# 01_MICRO.net
KiCad netlist of a schematic drawn in Altium Designer
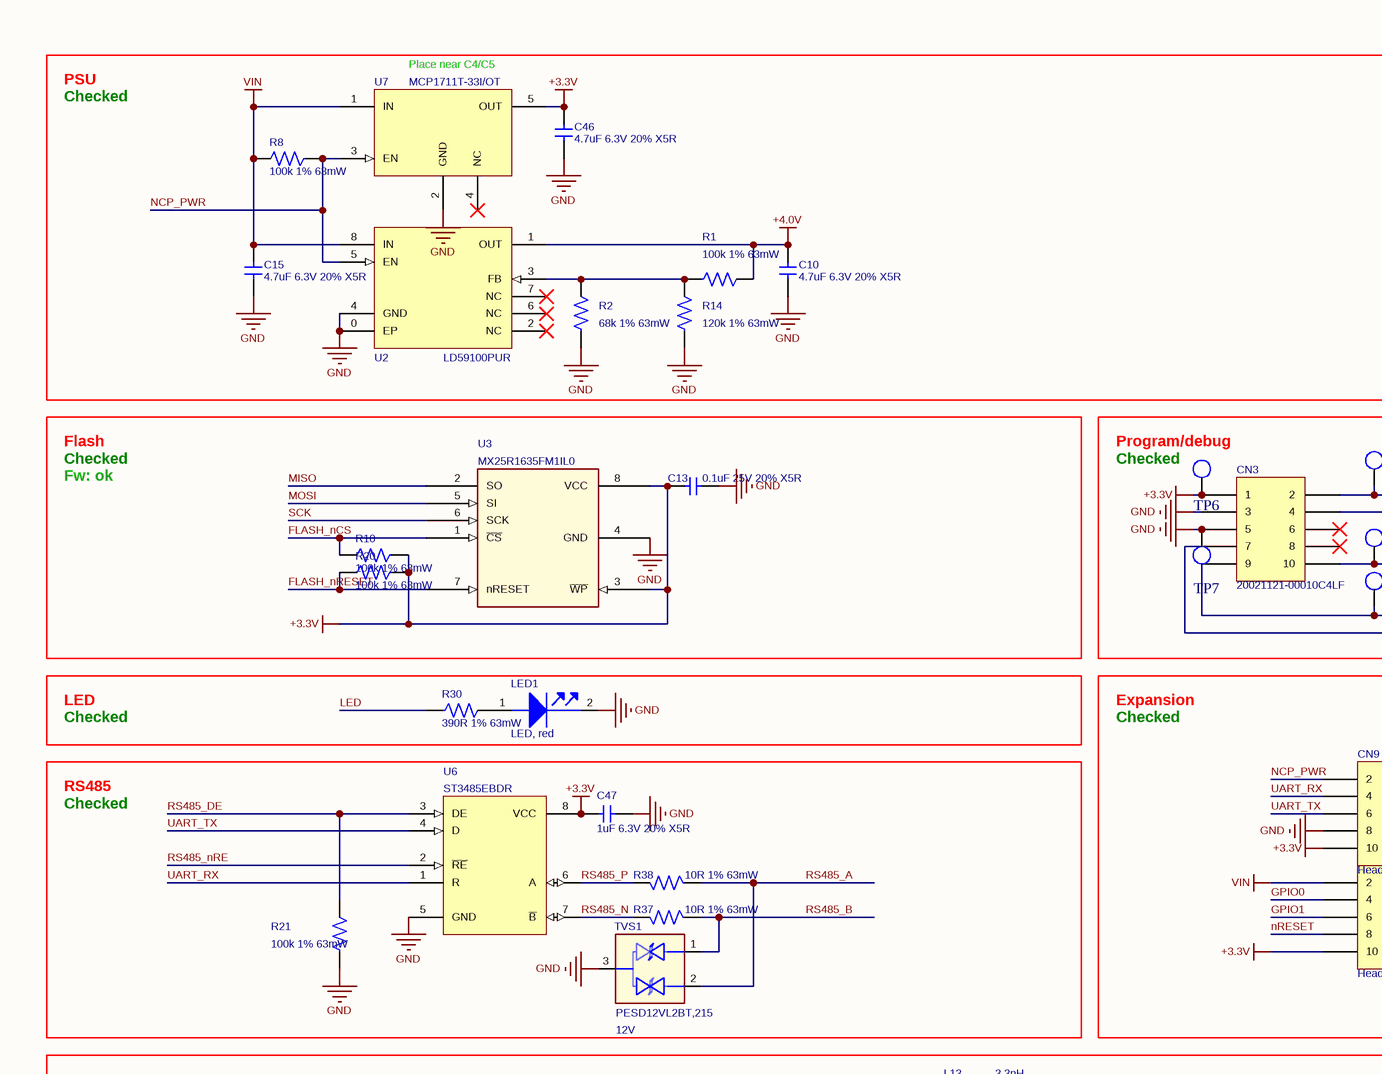
[diagram p0: 01_MICRO.SchDoc, top left]
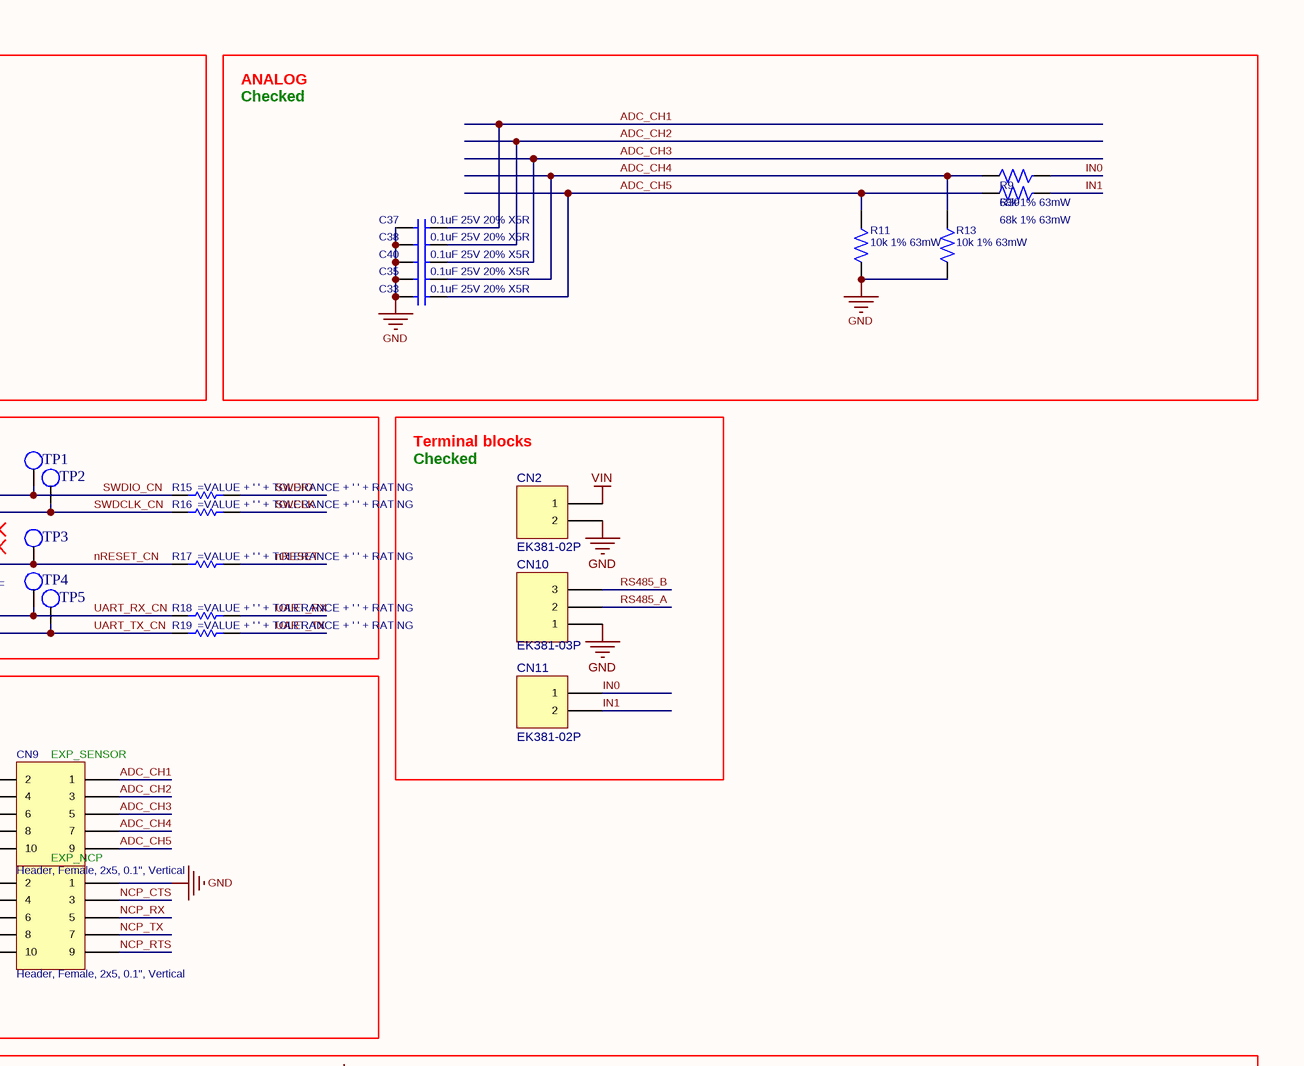
[diagram p1: 01_MICRO.SchDoc, top right]
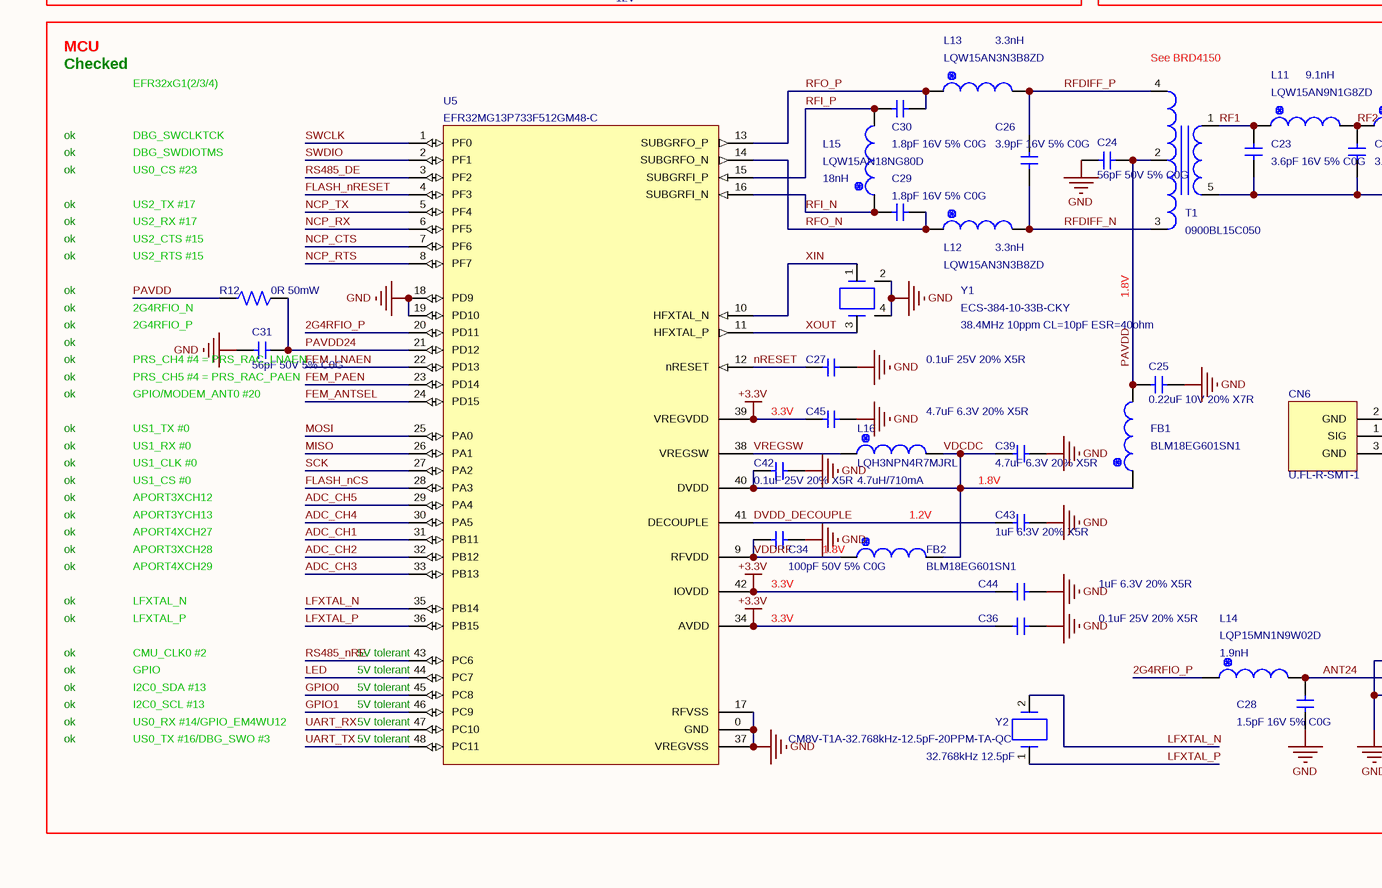
[diagram p2: 01_MICRO.SchDoc, bottom left]
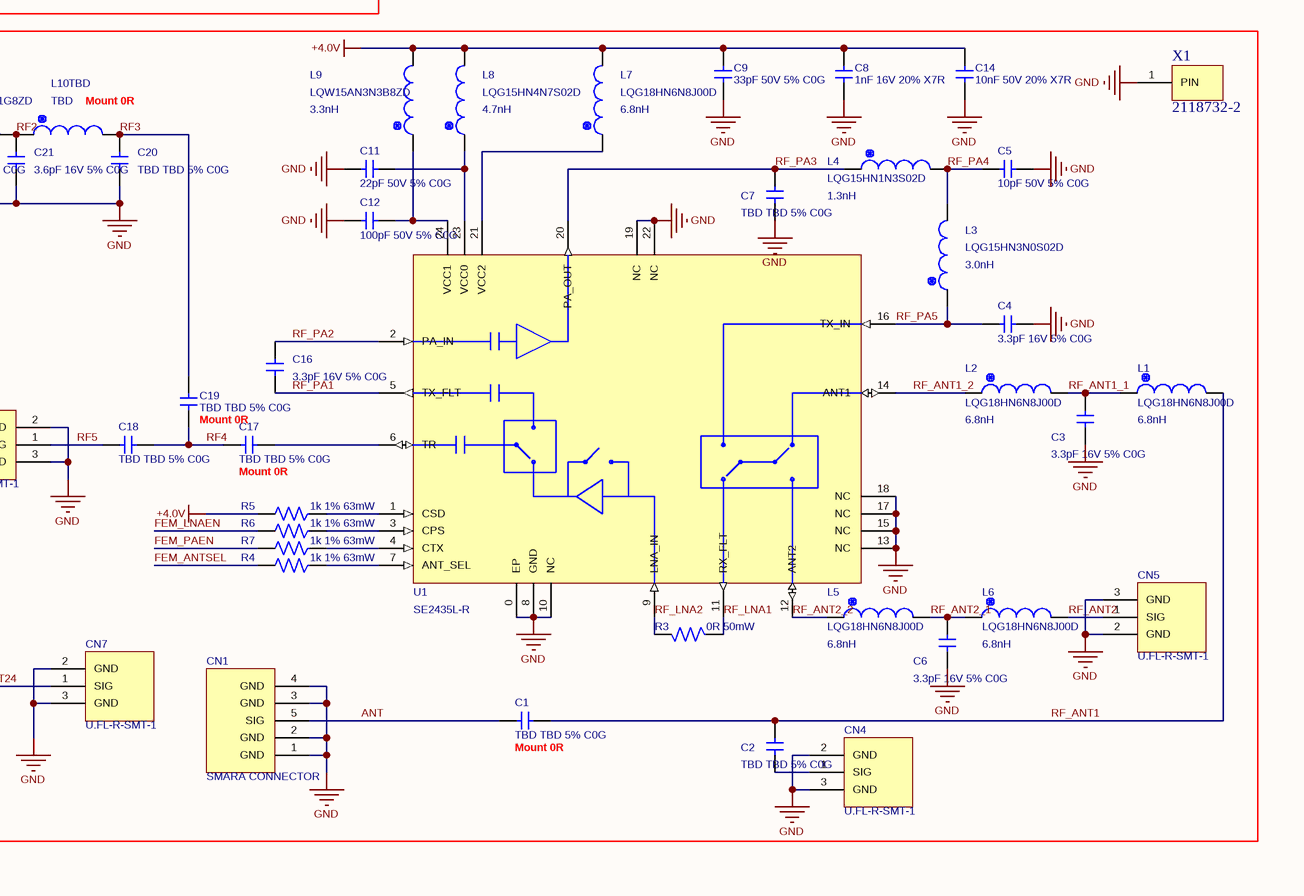
[diagram p3: 01_MICRO.SchDoc, bottom right]

(export (version "E")
  (design (tool "Eeschema 10.0.6"))
  (components
    (comp (ref "C1")
      (value "TBD TBD 5% C0G")
      (footprint "CAPC1005X55L")
      (description "Capacitor, ceramic")
      (fields
        (field (name "MFG") "<GENERIC>")
        (field (name "ASSEMBLYCOMMENTS") "Mount 0R")
        (field (name "TOLERANCE") "5%")
        (field (name "FOOTPRINT CHECKED") "Assign OK, Footprint OK")
      )
      (libsource (lib "*") (part "C_Dup1"))
    )
    (comp (ref "C2")
      (value "TBD TBD 5% C0G")
      (footprint "CAPC1005X55L")
      (description "Capacitor, ceramic")
      (fields
        (field (name "MFG") "<GENERIC>")
        (field (name "TOLERANCE") "5%")
        (field (name "FOOTPRINT CHECKED") "Assign OK, Footprint OK")
      )
      (libsource (lib "*") (part "C_Dup1"))
    )
    (comp (ref "C3")
      (value "3.3pF 16V 5% C0G")
      (footprint "CAPC1005X55L")
      (description "Capacitor, ceramic")
      (fields
        (field (name "MFG") "YAGEO")
        (field (name "TOLERANCE") "5%")
        (field (name "FOOTPRINT CHECKED") "Assign OK, Footprint OK")
      )
      (libsource (lib "*") (part "C_Dup1"))
    )
    (comp (ref "C4")
      (value "3.3pF 16V 5% C0G")
      (footprint "CAPC1005X55L")
      (description "Capacitor, ceramic")
      (fields
        (field (name "MFG") "YAGEO")
        (field (name "TOLERANCE") "5%")
        (field (name "FOOTPRINT CHECKED") "Assign OK, Footprint OK")
      )
      (libsource (lib "*") (part "C_Dup1"))
    )
    (comp (ref "C5")
      (value "10pF 50V 5% C0G")
      (footprint "CAPC1005X55L")
      (description "Capacitor, ceramic")
      (fields
        (field (name "MFG") "SAMSUNG")
        (field (name "TOLERANCE") "5%")
        (field (name "FOOTPRINT CHECKED") "Assign OK, Footprint OK")
      )
      (libsource (lib "*") (part "C_Dup1"))
    )
    (comp (ref "C6")
      (value "3.3pF 16V 5% C0G")
      (footprint "CAPC1005X55L")
      (description "Capacitor, ceramic")
      (fields
        (field (name "MFG") "YAGEO")
        (field (name "TOLERANCE") "5%")
        (field (name "FOOTPRINT CHECKED") "Assign OK, Footprint OK")
      )
      (libsource (lib "*") (part "C_Dup1"))
    )
    (comp (ref "C7")
      (value "TBD TBD 5% C0G")
      (footprint "CAPC1005X55L")
      (description "Capacitor, ceramic")
      (fields
        (field (name "MFG") "<GENERIC>")
        (field (name "TOLERANCE") "5%")
        (field (name "FOOTPRINT CHECKED") "Assign OK, Footprint OK")
      )
      (libsource (lib "*") (part "C_Dup1"))
    )
    (comp (ref "C8")
      (value "1nF 16V 20% X7R")
      (footprint "CAPC1005X55L")
      (description "Capacitor, ceramic")
      (fields
        (field (name "MFG") "SAMSUNG")
        (field (name "TOLERANCE") "20%")
        (field (name "FOOTPRINT CHECKED") "Assign OK, Footprint OK")
      )
      (libsource (lib "*") (part "C_Dup1"))
    )
    (comp (ref "C9")
      (value "33pF 50V 5% C0G")
      (footprint "CAPC1005X55L")
      (description "Capacitor, ceramic")
      (fields
        (field (name "MFG") "SAMSUNG")
        (field (name "TOLERANCE") "5%")
        (field (name "FOOTPRINT CHECKED") "Assign OK, Footprint OK")
      )
      (libsource (lib "*") (part "C_Dup1"))
    )
    (comp (ref "C10")
      (value "4.7uF 6.3V 20% X5R")
      (footprint "CAPC1608X90N")
      (description "Capacitor, ceramic")
      (fields
        (field (name "MFG") "SAMSUNG")
        (field (name "TOLERANCE") "20%")
        (field (name "FOOTPRINT CHECKED") "Assign OK, Footprint OK")
      )
      (libsource (lib "*") (part "C_Dup1"))
    )
    (comp (ref "C11")
      (value "22pF 50V 5% C0G")
      (footprint "CAPC1005X55L")
      (description "Capacitor, ceramic")
      (fields
        (field (name "MFG") "SAMSUNG")
        (field (name "TOLERANCE") "5%")
        (field (name "FOOTPRINT CHECKED") "Assign OK, Footprint OK")
      )
      (libsource (lib "*") (part "C_Dup1"))
    )
    (comp (ref "C12")
      (value "100pF 50V 5% C0G")
      (footprint "CAPC1005X55L")
      (description "Capacitor, ceramic")
      (fields
        (field (name "MFG") "SAMSUNG")
        (field (name "TOLERANCE") "5%")
        (field (name "FOOTPRINT CHECKED") "Assign OK, Footprint OK")
      )
      (libsource (lib "*") (part "C_Dup1"))
    )
    (comp (ref "C13")
      (value "0.1uF 25V 20% X5R")
      (footprint "CAPC1005N")
      (description "Capacitor, ceramic")
      (fields
        (field (name "MFG") "SAMSUNG")
        (field (name "TOLERANCE") "20%")
        (field (name "FOOTPRINT CHECKED") "Assign OK, Footprint OK")
      )
      (libsource (lib "*") (part "C_Dup1"))
    )
    (comp (ref "C14")
      (value "10nF 50V 20% X7R")
      (footprint "CAPC1005X55L")
      (description "Capacitor, ceramic")
      (fields
        (field (name "MFG") "SAMSUNG")
        (field (name "TOLERANCE") "20%")
        (field (name "FOOTPRINT CHECKED") "Assign OK, Footprint OK")
      )
      (libsource (lib "*") (part "C_Dup1"))
    )
    (comp (ref "C15")
      (value "4.7uF 6.3V 20% X5R")
      (footprint "CAPC1608X90N")
      (description "Capacitor, ceramic")
      (fields
        (field (name "MFG") "SAMSUNG")
        (field (name "TOLERANCE") "20%")
        (field (name "FOOTPRINT CHECKED") "Assign OK, Footprint OK")
      )
      (libsource (lib "*") (part "C_Dup1"))
    )
    (comp (ref "C16")
      (value "3.3pF 16V 5% C0G")
      (footprint "CAPC1005X55L")
      (description "Capacitor, ceramic")
      (fields
        (field (name "MFG") "YAGEO")
        (field (name "TOLERANCE") "5%")
        (field (name "FOOTPRINT CHECKED") "Assign OK, Footprint OK")
      )
      (libsource (lib "*") (part "C_Dup1"))
    )
    (comp (ref "C17")
      (value "TBD TBD 5% C0G")
      (footprint "CAPC1005X55L")
      (description "Capacitor, ceramic")
      (fields
        (field (name "MFG") "<GENERIC>")
        (field (name "ASSEMBLYCOMMENTS") "Mount 0R")
        (field (name "TOLERANCE") "5%")
        (field (name "FOOTPRINT CHECKED") "Assign OK, Footprint OK")
      )
      (libsource (lib "*") (part "C_Dup1"))
    )
    (comp (ref "C18")
      (value "TBD TBD 5% C0G")
      (footprint "CAPC1005X55L")
      (description "Capacitor, ceramic")
      (fields
        (field (name "MFG") "<GENERIC>")
        (field (name "TOLERANCE") "5%")
        (field (name "FOOTPRINT CHECKED") "Assign OK, Footprint OK")
      )
      (libsource (lib "*") (part "C_Dup1"))
    )
    (comp (ref "C19")
      (value "TBD TBD 5% C0G")
      (footprint "CAPC1005X55L")
      (description "Capacitor, ceramic")
      (fields
        (field (name "MFG") "<GENERIC>")
        (field (name "ASSEMBLYCOMMENTS") "Mount 0R")
        (field (name "TOLERANCE") "5%")
        (field (name "FOOTPRINT CHECKED") "Assign OK, Footprint OK")
      )
      (libsource (lib "*") (part "C_Dup1"))
    )
    (comp (ref "C20")
      (value "TBD TBD 5% C0G")
      (footprint "CAPC1005X55L")
      (description "Capacitor, ceramic")
      (fields
        (field (name "MFG") "<GENERIC>")
        (field (name "TOLERANCE") "5%")
        (field (name "FOOTPRINT CHECKED") "Assign OK, Footprint OK")
      )
      (libsource (lib "*") (part "C_Dup1"))
    )
    (comp (ref "C21")
      (value "3.6pF 16V 5% C0G")
      (footprint "CAPC1005X55L")
      (description "Capacitor, ceramic")
      (fields
        (field (name "MFG") "YAGEO")
        (field (name "TOLERANCE") "5%")
        (field (name "FOOTPRINT CHECKED") "Assign OK, Footprint OK")
      )
      (libsource (lib "*") (part "C_Dup1"))
    )
    (comp (ref "C23")
      (value "3.6pF 16V 5% C0G")
      (footprint "CAPC1005X55L")
      (description "Capacitor, ceramic")
      (fields
        (field (name "MFG") "YAGEO")
        (field (name "TOLERANCE") "5%")
        (field (name "FOOTPRINT CHECKED") "Assign OK, Footprint OK")
      )
      (libsource (lib "*") (part "C_Dup1"))
    )
    (comp (ref "C24")
      (value "56pF 50V 5% C0G")
      (footprint "CAPC1005X55L")
      (description "Capacitor, ceramic")
      (fields
        (field (name "MFG") "SAMSUNG")
        (field (name "TOLERANCE") "5%")
        (field (name "FOOTPRINT CHECKED") "Assign OK, Footprint OK")
      )
      (libsource (lib "*") (part "C_Dup1"))
    )
    (comp (ref "C25")
      (value "0.22uF 10V 20% X7R")
      (footprint "CAPC1005N")
      (description "Capacitor, ceramic")
      (fields
        (field (name "MFG") "SAMSUNG")
        (field (name "TOLERANCE") "20%")
        (field (name "FOOTPRINT CHECKED") "Assign OK, Footprint OK")
      )
      (libsource (lib "*") (part "C_Dup1"))
    )
    (comp (ref "C26")
      (value "3.9pF 16V 5% C0G")
      (footprint "CAPC1005X55L")
      (description "Capacitor, ceramic")
      (fields
        (field (name "MFG") "YAGEO")
        (field (name "TOLERANCE") "5%")
        (field (name "FOOTPRINT CHECKED") "Assign OK, Footprint OK")
      )
      (libsource (lib "*") (part "C_Dup1"))
    )
    (comp (ref "C27")
      (value "0.1uF 25V 20% X5R")
      (footprint "CAPC1005N")
      (description "Capacitor, ceramic")
      (fields
        (field (name "MFG") "SAMSUNG")
        (field (name "TOLERANCE") "20%")
        (field (name "FOOTPRINT CHECKED") "Assign OK, Footprint OK")
      )
      (libsource (lib "*") (part "C_Dup1"))
    )
    (comp (ref "C28")
      (value "1.5pF 16V 5% C0G")
      (footprint "CAPC1005X55L")
      (description "Capacitor, ceramic")
      (fields
        (field (name "MFG") "YAGEO")
        (field (name "TOLERANCE") "5%")
        (field (name "FOOTPRINT CHECKED") "Assign OK, Footprint OK")
      )
      (libsource (lib "*") (part "C_Dup1"))
    )
    (comp (ref "C29")
      (value "1.8pF 16V 5% C0G")
      (footprint "CAPC1005X55L")
      (description "Capacitor, ceramic")
      (fields
        (field (name "MFG") "YAGEO")
        (field (name "TOLERANCE") "5%")
        (field (name "FOOTPRINT CHECKED") "Assign OK, Footprint OK")
      )
      (libsource (lib "*") (part "C_Dup1"))
    )
    (comp (ref "C30")
      (value "1.8pF 16V 5% C0G")
      (footprint "CAPC1005X55L")
      (description "Capacitor, ceramic")
      (fields
        (field (name "MFG") "YAGEO")
        (field (name "TOLERANCE") "5%")
        (field (name "FOOTPRINT CHECKED") "Assign OK, Footprint OK")
      )
      (libsource (lib "*") (part "C_Dup1"))
    )
    (comp (ref "C31")
      (value "56pF 50V 5% C0G")
      (footprint "CAPC1005X55L")
      (description "Capacitor, ceramic")
      (fields
        (field (name "MFG") "SAMSUNG")
        (field (name "TOLERANCE") "5%")
        (field (name "FOOTPRINT CHECKED") "Assign OK, Footprint OK")
      )
      (libsource (lib "*") (part "C_Dup1"))
    )
    (comp (ref "C33")
      (value "0.1uF 25V 20% X5R")
      (footprint "CAPC1005N")
      (description "Capacitor, ceramic")
      (fields
        (field (name "MFG") "SAMSUNG")
        (field (name "TOLERANCE") "20%")
        (field (name "FOOTPRINT CHECKED") "Assign OK, Footprint OK")
      )
      (libsource (lib "*") (part "C_Dup1"))
    )
    (comp (ref "C34")
      (value "100pF 50V 5% C0G")
      (footprint "CAPC1005X55L")
      (description "Capacitor, ceramic")
      (fields
        (field (name "MFG") "SAMSUNG")
        (field (name "TOLERANCE") "5%")
        (field (name "FOOTPRINT CHECKED") "Assign OK, Footprint OK")
      )
      (libsource (lib "*") (part "C_Dup1"))
    )
    (comp (ref "C35")
      (value "0.1uF 25V 20% X5R")
      (footprint "CAPC1005N")
      (description "Capacitor, ceramic")
      (fields
        (field (name "MFG") "SAMSUNG")
        (field (name "TOLERANCE") "20%")
        (field (name "FOOTPRINT CHECKED") "Assign OK, Footprint OK")
      )
      (libsource (lib "*") (part "C_Dup1"))
    )
    (comp (ref "C36")
      (value "0.1uF 25V 20% X5R")
      (footprint "CAPC1005N")
      (description "Capacitor, ceramic")
      (fields
        (field (name "MFG") "SAMSUNG")
        (field (name "TOLERANCE") "20%")
        (field (name "FOOTPRINT CHECKED") "Assign OK, Footprint OK")
      )
      (libsource (lib "*") (part "C_Dup1"))
    )
    (comp (ref "C37")
      (value "0.1uF 25V 20% X5R")
      (footprint "CAPC1005N")
      (description "Capacitor, ceramic")
      (fields
        (field (name "MFG") "SAMSUNG")
        (field (name "TOLERANCE") "20%")
        (field (name "FOOTPRINT CHECKED") "Assign OK, Footprint OK")
      )
      (libsource (lib "*") (part "C_Dup1"))
    )
    (comp (ref "C38")
      (value "0.1uF 25V 20% X5R")
      (footprint "CAPC1005N")
      (description "Capacitor, ceramic")
      (fields
        (field (name "MFG") "SAMSUNG")
        (field (name "TOLERANCE") "20%")
        (field (name "FOOTPRINT CHECKED") "Assign OK, Footprint OK")
      )
      (libsource (lib "*") (part "C_Dup1"))
    )
    (comp (ref "C39")
      (value "4.7uF 6.3V 20% X5R")
      (footprint "CAPC1608X90N")
      (description "Capacitor, ceramic")
      (fields
        (field (name "MFG") "SAMSUNG")
        (field (name "TOLERANCE") "20%")
        (field (name "FOOTPRINT CHECKED") "Assign OK, Footprint OK")
      )
      (libsource (lib "*") (part "C_Dup1"))
    )
    (comp (ref "C40")
      (value "0.1uF 25V 20% X5R")
      (footprint "CAPC1005N")
      (description "Capacitor, ceramic")
      (fields
        (field (name "MFG") "SAMSUNG")
        (field (name "TOLERANCE") "20%")
        (field (name "FOOTPRINT CHECKED") "Assign OK, Footprint OK")
      )
      (libsource (lib "*") (part "C_Dup1"))
    )
    (comp (ref "C42")
      (value "0.1uF 25V 20% X5R")
      (footprint "CAPC1005N")
      (description "Capacitor, ceramic")
      (fields
        (field (name "MFG") "SAMSUNG")
        (field (name "TOLERANCE") "20%")
        (field (name "FOOTPRINT CHECKED") "Assign OK, Footprint OK")
      )
      (libsource (lib "*") (part "C_Dup1"))
    )
    (comp (ref "C43")
      (value "1uF 6.3V 20% X5R")
      (footprint "CAPC1005N")
      (description "Capacitor, ceramic")
      (fields
        (field (name "MFG") "SAMSUNG")
        (field (name "TOLERANCE") "20%")
        (field (name "FOOTPRINT CHECKED") "Assign OK, Footprint OK")
      )
      (libsource (lib "*") (part "C_Dup1"))
    )
    (comp (ref "C44")
      (value "1uF 6.3V 20% X5R")
      (footprint "CAPC1005N")
      (description "Capacitor, ceramic")
      (fields
        (field (name "MFG") "SAMSUNG")
        (field (name "TOLERANCE") "20%")
        (field (name "FOOTPRINT CHECKED") "Assign OK, Footprint OK")
      )
      (libsource (lib "*") (part "C_Dup1"))
    )
    (comp (ref "C45")
      (value "4.7uF 6.3V 20% X5R")
      (footprint "CAPC1608X90N")
      (description "Capacitor, ceramic")
      (fields
        (field (name "MFG") "SAMSUNG")
        (field (name "TOLERANCE") "20%")
        (field (name "FOOTPRINT CHECKED") "Assign OK, Footprint OK")
      )
      (libsource (lib "*") (part "C_Dup1"))
    )
    (comp (ref "C46")
      (value "4.7uF 6.3V 20% X5R")
      (footprint "CAPC1608X90N")
      (description "Capacitor, ceramic")
      (fields
        (field (name "MFG") "SAMSUNG")
        (field (name "TOLERANCE") "20%")
        (field (name "FOOTPRINT CHECKED") "Assign OK, Footprint OK")
      )
      (libsource (lib "*") (part "C_Dup1"))
    )
    (comp (ref "C47")
      (value "1uF 6.3V 20% X5R")
      (footprint "CAPC1005N")
      (description "Capacitor, ceramic")
      (fields
        (field (name "MFG") "SAMSUNG")
        (field (name "TOLERANCE") "20%")
        (field (name "FOOTPRINT CHECKED") "Assign OK, Footprint OK")
      )
      (libsource (lib "*") (part "C_Dup1"))
    )
    (comp (ref "CN1")
      (value "SMARA CONNECTOR")
      (footprint "0733910320")
      (description "SMA, Right angle")
      (fields (field (name "MFG") "LPRS") (field (name "FOOTPRINT CHECKED") "Assign OK, Footprint OK"))
      (libsource (lib "xct") (part "RPSMA"))
    )
    (comp (ref "CN2")
      (value "EK381-02P")
      (footprint "EK381-02P")
      (description "Header, 2-Pin")
      (fields (field (name "MFG") "DINKLE") (field (name "FOOTPRINT CHECKED") "Assign OK, Footprint OK"))
      (libsource (lib "Miscellaneous Connectors") (part "Header 2"))
    )
    (comp (ref "CN3")
      (value "20021121-00010C4LF")
      (footprint "SensorWireless:HDR2X5")
      (description "Connector Header Surface Mount 10 position 0.050\" (1.27mm)")
      (fields (field (name "MFG") "AMPHENOL") (field (name "FOOTPRINT CHECKED") "Assign Ok, Footprint Ok"))
      (libsource (lib "") (part "Header 5X2_1"))
    )
    (comp (ref "CN4")
      (value "U.FL-R-SMT-1")
      (footprint "U.FL-R-SMT-1")
      (description "Ultra Small Surface Mount Coaxial Connectors - 1.9mm or 2.4mm Mated Height")
      (fields (field (name "MFG") "HIROSE") (field (name "FOOTPRINT CHECKED") "Assign OK, Footprint OK"))
      (libsource (lib "") (part "U.FL-R-SMT-1_1"))
    )
    (comp (ref "CN5")
      (value "U.FL-R-SMT-1")
      (footprint "U.FL-R-SMT-1")
      (description "Ultra Small Surface Mount Coaxial Connectors - 1.9mm or 2.4mm Mated Height")
      (fields (field (name "MFG") "HIROSE") (field (name "FOOTPRINT CHECKED") "Assign OK, Footprint OK"))
      (libsource (lib "traz") (part "U.FL-R-SMT-1"))
    )
    (comp (ref "CN6")
      (value "U.FL-R-SMT-1")
      (footprint "U.FL-R-SMT-1")
      (description "Ultra Small Surface Mount Coaxial Connectors - 1.9mm or 2.4mm Mated Height")
      (fields (field (name "MFG") "HIROSE") (field (name "FOOTPRINT CHECKED") "Assign OK, Footprint OK"))
      (libsource (lib "") (part "U.FL-R-SMT-1_2"))
    )
    (comp (ref "CN7")
      (value "U.FL-R-SMT-1")
      (footprint "U.FL-R-SMT-1")
      (description "Ultra Small Surface Mount Coaxial Connectors - 1.9mm or 2.4mm Mated Height")
      (fields (field (name "MFG") "HIROSE") (field (name "FOOTPRINT CHECKED") "Assign OK, Footprint OK"))
      (libsource (lib "") (part "U.FL-R-SMT-1_1"))
    )
    (comp (ref "CN8")
      (value "Header, Female, 2x5, 0.1\", Vertical")
      (fields (field (name "MFG") "<GENERIC>") (field (name "FOOTPRINT CHECKED") "Assign Ok, Footprint Ok"))
      (libsource (lib "Miscellaneous Connectors") (part "Header 5X2"))
    )
    (comp (ref "CN9")
      (value "Header, Female, 2x5, 0.1\", Vertical")
      (fields (field (name "MFG") "<GENERIC>") (field (name "FOOTPRINT CHECKED") "Assign Ok, Footprint Ok"))
      (libsource (lib "Miscellaneous Connectors") (part "Header 5X2"))
    )
    (comp (ref "CN10")
      (value "EK381-03P")
      (footprint "EK381-03P")
      (description "Header, 3-Pin")
      (fields (field (name "MFG") "DINKLE") (field (name "FOOTPRINT CHECKED") "Assign OK, Footprint OK"))
      (libsource (lib "Miscellaneous Connectors") (part "Header 3"))
    )
    (comp (ref "CN11")
      (value "EK381-02P")
      (footprint "EK381-02P")
      (description "Header, 2-Pin")
      (fields (field (name "MFG") "DINKLE") (field (name "FOOTPRINT CHECKED") "Assign OK, Footprint OK"))
      (libsource (lib "Miscellaneous Connectors") (part "Header 2"))
    )
    (comp (ref "FB1")
      (value "BLM18EG601SN1")
      (footprint "INDC1608X95N")
      (description "Ferrite bead")
      (fields (field (name "MFG") "MURATA") (field (name "FOOTPRINT CHECKED") "Assign OK, Footprint OK"))
      (libsource (lib "*") (part "L"))
    )
    (comp (ref "FB2")
      (value "BLM18EG601SN1")
      (footprint "INDC1608X95N")
      (description "Ferrite bead")
      (fields (field (name "MFG") "MURATA") (field (name "FOOTPRINT CHECKED") "Assign OK, Footprint OK"))
      (libsource (lib "*") (part "L"))
    )
    (comp (ref "L1")
      (value "LQG18HN6N8J00D")
      (footprint "INDC1608X95N")
      (description "Inductor")
      (fields
        (field (name "MFG") "MURATA")
        (field (name "ALTIUM_VALUE") "6.8nH")
        (field (name "TOLERANCE") "TBD%")
        (field (name "FOOTPRINT CHECKED") "Assign OK, Footprint OK")
      )
      (libsource (lib "*") (part "L"))
    )
    (comp (ref "L2")
      (value "LQG18HN6N8J00D")
      (footprint "INDC1608X95N")
      (description "Inductor")
      (fields
        (field (name "MFG") "MURATA")
        (field (name "ALTIUM_VALUE") "6.8nH")
        (field (name "TOLERANCE") "TBD%")
        (field (name "FOOTPRINT CHECKED") "Assign OK, Footprint OK")
      )
      (libsource (lib "*") (part "L"))
    )
    (comp (ref "L3")
      (value "LQG15HN3N0S02D")
      (footprint "INDC1005X55L")
      (description "Inductor")
      (fields
        (field (name "MFG") "MURATA")
        (field (name "ALTIUM_VALUE") "3.0nH")
        (field (name "TOLERANCE") "TBD%")
        (field (name "FOOTPRINT CHECKED") "Assign OK, Footprint OK")
      )
      (libsource (lib "*") (part "L"))
    )
    (comp (ref "L4")
      (value "LQG15HN1N3S02D")
      (footprint "INDC1005X55L")
      (description "Inductor")
      (fields
        (field (name "MFG") "MURATA")
        (field (name "ALTIUM_VALUE") "1.3nH")
        (field (name "TOLERANCE") "TBD%")
        (field (name "FOOTPRINT CHECKED") "Assign OK, Footprint OK")
      )
      (libsource (lib "*") (part "L"))
    )
    (comp (ref "L5")
      (value "LQG18HN6N8J00D")
      (footprint "INDC1608X95N")
      (description "Inductor")
      (fields
        (field (name "MFG") "MURATA")
        (field (name "ALTIUM_VALUE") "6.8nH")
        (field (name "TOLERANCE") "TBD%")
        (field (name "FOOTPRINT CHECKED") "Assign OK, Footprint OK")
      )
      (libsource (lib "*") (part "L"))
    )
    (comp (ref "L6")
      (value "LQG18HN6N8J00D")
      (footprint "INDC1608X95N")
      (description "Inductor")
      (fields
        (field (name "MFG") "MURATA")
        (field (name "ALTIUM_VALUE") "6.8nH")
        (field (name "TOLERANCE") "TBD%")
        (field (name "FOOTPRINT CHECKED") "Assign OK, Footprint OK")
      )
      (libsource (lib "*") (part "L"))
    )
    (comp (ref "L7")
      (value "LQG18HN6N8J00D")
      (footprint "INDC1608X95N")
      (description "Inductor")
      (fields
        (field (name "MFG") "MURATA")
        (field (name "ALTIUM_VALUE") "6.8nH")
        (field (name "TOLERANCE") "TBD%")
        (field (name "FOOTPRINT CHECKED") "Assign OK, Footprint OK")
      )
      (libsource (lib "*") (part "L"))
    )
    (comp (ref "L8")
      (value "LQG15HN4N7S02D")
      (footprint "INDC1005X55L")
      (description "Inductor")
      (fields
        (field (name "MFG") "MURATA")
        (field (name "ALTIUM_VALUE") "4.7nH")
        (field (name "TOLERANCE") "TBD%")
        (field (name "FOOTPRINT CHECKED") "Assign OK, Footprint OK")
      )
      (libsource (lib "*") (part "L"))
    )
    (comp (ref "L9")
      (value "LQW15AN3N3B8ZD")
      (footprint "INDC1005X55L")
      (description "Inductor")
      (fields
        (field (name "MFG") "MURATA")
        (field (name "ALTIUM_VALUE") "3.3nH")
        (field (name "TOLERANCE") "TBD%")
        (field (name "FOOTPRINT CHECKED") "Assign OK, Footprint OK")
      )
      (libsource (lib "*") (part "L"))
    )
    (comp (ref "L10")
      (value "TBD")
      (footprint "INDC1005X55L")
      (description "Inductor")
      (fields
        (field (name "ASSEMBLYCOMMENTS") "Mount 0R")
        (field (name "ALTIUM_VALUE") "TBD")
        (field (name "TOLERANCE") "TBD%")
        (field (name "FOOTPRINT CHECKED") "Assign OK, Footprint OK")
      )
      (libsource (lib "*") (part "L"))
    )
    (comp (ref "L11")
      (value "LQW15AN9N1G8ZD")
      (footprint "INDC1005X55L")
      (description "Inductor")
      (fields
        (field (name "MFG") "MURATA")
        (field (name "ALTIUM_VALUE") "9.1nH")
        (field (name "TOLERANCE") "TBD%")
        (field (name "FOOTPRINT CHECKED") "Assign OK, Footprint OK")
      )
      (libsource (lib "*") (part "L"))
    )
    (comp (ref "L12")
      (value "LQW15AN3N3B8ZD")
      (footprint "INDC1005X55L")
      (description "Inductor")
      (fields
        (field (name "MFG") "MURATA")
        (field (name "ALTIUM_VALUE") "3.3nH")
        (field (name "TOLERANCE") "TBD%")
        (field (name "FOOTPRINT CHECKED") "Assign OK, Footprint OK")
      )
      (libsource (lib "*") (part "L"))
    )
    (comp (ref "L13")
      (value "LQW15AN3N3B8ZD")
      (footprint "INDC1005X55L")
      (description "Inductor")
      (fields
        (field (name "MFG") "MURATA")
        (field (name "ALTIUM_VALUE") "3.3nH")
        (field (name "TOLERANCE") "TBD%")
        (field (name "FOOTPRINT CHECKED") "Assign OK, Footprint OK")
      )
      (libsource (lib "*") (part "L"))
    )
    (comp (ref "L14")
      (value "LQP15MN1N9W02D")
      (footprint "INDC1005X55L")
      (description "Inductor")
      (fields
        (field (name "MFG") "MURATA")
        (field (name "ALTIUM_VALUE") "1.9nH")
        (field (name "TOLERANCE") "TBD%")
        (field (name "FOOTPRINT CHECKED") "Assign OK, Footprint OK")
      )
      (libsource (lib "*") (part "L"))
    )
    (comp (ref "L15")
      (value "LQW15AN18NG80D")
      (footprint "INDC1005X55L")
      (description "Inductor")
      (fields
        (field (name "MFG") "MURATA")
        (field (name "ALTIUM_VALUE") "18nH")
        (field (name "TOLERANCE") "TBD%")
        (field (name "FOOTPRINT CHECKED") "Assign OK, Footprint OK")
      )
      (libsource (lib "*") (part "L"))
    )
    (comp (ref "L16")
      (value "LQH3NPN4R7MJRL")
      (footprint "INDW3030N")
      (description "Inductor")
      (fields
        (field (name "MFG") "MURATA")
        (field (name "ALTIUM_VALUE") "4.7uH/710mA")
        (field (name "TOLERANCE") "TBD%")
        (field (name "FOOTPRINT CHECKED") "Assign OK, Footprint OK")
      )
      (libsource (lib "*") (part "L"))
    )
    (comp (ref "LED1")
      (value "LED, red")
      (footprint "LEDC2012N")
      (fields (field (name "MFG") "<GENERIC>") (field (name "FOOTPRINT CHECKED") "Assign OK, Footprint OK"))
      (libsource (lib "*") (part "Led Red HSMC-C170"))
    )
    (comp (ref "R1")
      (value "100k 1% 63mW")
      (footprint "RESC1608X40N")
      (description "Resistor, SMD")
      (fields
        (field (name "MFG") "<GENERIC>")
        (field (name "TOLERANCE") "1%")
        (field (name "FOOTPRINT CHECKED") "Assign OK, Footprint OK")
      )
      (libsource (lib "*") (part "R"))
    )
    (comp (ref "R2")
      (value "68k 1% 63mW")
      (footprint "RESC1608X40N")
      (description "Resistor, SMD")
      (fields
        (field (name "MFG") "<GENERIC>")
        (field (name "TOLERANCE") "1%")
        (field (name "FOOTPRINT CHECKED") "Assign OK, Footprint OK")
      )
      (libsource (lib "*") (part "R"))
    )
    (comp (ref "R3")
      (value "0R 50mW")
      (footprint "RESC1005X40N")
      (description "Resistor, SMD")
      (fields
        (field (name "MFG") "<GENERIC>")
        (field (name "POWER") "50mW")
        (field (name "FOOTPRINT CHECKED") "Assign OK, Footprint OK")
      )
      (libsource (lib "*") (part "R"))
    )
    (comp (ref "R4")
      (value "1k 1% 63mW")
      (footprint "RESC1608X40N")
      (description "Resistor, SMD")
      (fields
        (field (name "MFG") "<GENERIC>")
        (field (name "TOLERANCE") "1%")
        (field (name "FOOTPRINT CHECKED") "Assign OK, Footprint OK")
      )
      (libsource (lib "*") (part "R"))
    )
    (comp (ref "R5")
      (value "1k 1% 63mW")
      (footprint "RESC1608X40N")
      (description "Resistor, SMD")
      (fields
        (field (name "MFG") "<GENERIC>")
        (field (name "TOLERANCE") "1%")
        (field (name "FOOTPRINT CHECKED") "Assign OK, Footprint OK")
      )
      (libsource (lib "*") (part "R"))
    )
    (comp (ref "R6")
      (value "1k 1% 63mW")
      (footprint "RESC1608X40N")
      (description "Resistor, SMD")
      (fields
        (field (name "MFG") "<GENERIC>")
        (field (name "TOLERANCE") "1%")
        (field (name "FOOTPRINT CHECKED") "Assign OK, Footprint OK")
      )
      (libsource (lib "*") (part "R"))
    )
    (comp (ref "R7")
      (value "1k 1% 63mW")
      (footprint "RESC1608X40N")
      (description "Resistor, SMD")
      (fields
        (field (name "MFG") "<GENERIC>")
        (field (name "TOLERANCE") "1%")
        (field (name "FOOTPRINT CHECKED") "Assign OK, Footprint OK")
      )
      (libsource (lib "*") (part "R"))
    )
    (comp (ref "R8")
      (value "100k 1% 63mW")
      (footprint "RESC1608X40N")
      (description "Resistor, SMD")
      (fields
        (field (name "MFG") "<GENERIC>")
        (field (name "TOLERANCE") "1%")
        (field (name "FOOTPRINT CHECKED") "Assign OK, Footprint OK")
      )
      (libsource (lib "*") (part "R"))
    )
    (comp (ref "R9")
      (value "68k 1% 63mW")
      (footprint "RESC1608X40N")
      (description "Resistor, SMD")
      (fields
        (field (name "MFG") "<GENERIC>")
        (field (name "TOLERANCE") "1%")
        (field (name "FOOTPRINT CHECKED") "Assign OK, Footprint OK")
      )
      (libsource (lib "*") (part "R"))
    )
    (comp (ref "R10")
      (value "100k 1% 63mW")
      (footprint "RESC1608X40N")
      (description "Resistor, SMD")
      (fields
        (field (name "MFG") "<GENERIC>")
        (field (name "TOLERANCE") "1%")
        (field (name "FOOTPRINT CHECKED") "Assign OK, Footprint OK")
      )
      (libsource (lib "*") (part "R"))
    )
    (comp (ref "R11")
      (value "10k 1% 63mW")
      (footprint "RESC1608X40N")
      (description "Resistor, SMD")
      (fields
        (field (name "MFG") "<GENERIC>")
        (field (name "TOLERANCE") "1%")
        (field (name "FOOTPRINT CHECKED") "Assign OK, Footprint OK")
      )
      (libsource (lib "*") (part "R"))
    )
    (comp (ref "R12")
      (value "0R 50mW")
      (footprint "RESC1005X40N")
      (description "Resistor, SMD")
      (fields
        (field (name "MFG") "<GENERIC>")
        (field (name "POWER") "50mW")
        (field (name "FOOTPRINT CHECKED") "Assign OK, Footprint OK")
      )
      (libsource (lib "*") (part "R"))
    )
    (comp (ref "R13")
      (value "10k 1% 63mW")
      (footprint "RESC1608X40N")
      (description "Resistor, SMD")
      (fields
        (field (name "MFG") "<GENERIC>")
        (field (name "TOLERANCE") "1%")
        (field (name "FOOTPRINT CHECKED") "Assign OK, Footprint OK")
      )
      (libsource (lib "*") (part "R"))
    )
    (comp (ref "R14")
      (value "120k 1% 63mW")
      (footprint "RESC1608X40N")
      (description "Resistor, SMD")
      (fields
        (field (name "MFG") "<GENERIC>")
        (field (name "TOLERANCE") "1%")
        (field (name "FOOTPRINT CHECKED") "Assign OK, Footprint OK")
      )
      (libsource (lib "*") (part "R"))
    )
    (comp (ref "R15")
      (value "47R 1%")
      (footprint "RESC1608X40N")
      (description "Resistor, SMD")
      (fields
        (field (name "MFG") "<GENERIC>")
        (field (name "TOLERANCE") "1%")
        (field (name "FOOTPRINT CHECKED") "Assign Ok, Footprint Ok")
      )
      (libsource (lib "SensorWireless") (part "RES"))
    )
    (comp (ref "R16")
      (value "47R 1%")
      (footprint "RESC1608X40N")
      (description "Resistor, SMD")
      (fields
        (field (name "MFG") "<GENERIC>")
        (field (name "TOLERANCE") "1%")
        (field (name "FOOTPRINT CHECKED") "Assign Ok, Footprint Ok")
      )
      (libsource (lib "SensorWireless") (part "RES"))
    )
    (comp (ref "R17")
      (value "47R 1%")
      (footprint "RESC1608X40N")
      (description "Resistor, SMD")
      (fields
        (field (name "MFG") "<GENERIC>")
        (field (name "TOLERANCE") "1%")
        (field (name "FOOTPRINT CHECKED") "Assign Ok, Footprint Ok")
      )
      (libsource (lib "SensorWireless") (part "RES"))
    )
    (comp (ref "R18")
      (value "47R 1%")
      (footprint "RESC1608X40N")
      (description "Resistor, SMD")
      (fields
        (field (name "MFG") "<GENERIC>")
        (field (name "TOLERANCE") "1%")
        (field (name "FOOTPRINT CHECKED") "Assign Ok, Footprint Ok")
      )
      (libsource (lib "SensorWireless") (part "RES"))
    )
    (comp (ref "R19")
      (value "47R 1%")
      (footprint "RESC1608X40N")
      (description "Resistor, SMD")
      (fields
        (field (name "MFG") "<GENERIC>")
        (field (name "TOLERANCE") "1%")
        (field (name "FOOTPRINT CHECKED") "Assign Ok, Footprint Ok")
      )
      (libsource (lib "SensorWireless") (part "RES"))
    )
    (comp (ref "R20")
      (value "100k 1% 63mW")
      (footprint "RESC1608X40N")
      (description "Resistor, SMD")
      (fields
        (field (name "MFG") "<GENERIC>")
        (field (name "TOLERANCE") "1%")
        (field (name "FOOTPRINT CHECKED") "Assign OK, Footprint OK")
      )
      (libsource (lib "*") (part "R"))
    )
    (comp (ref "R21")
      (value "100k 1% 63mW")
      (footprint "RESC1608X40N")
      (description "Resistor, SMD")
      (fields
        (field (name "MFG") "<GENERIC>")
        (field (name "TOLERANCE") "1%")
        (field (name "FOOTPRINT CHECKED") "Assign OK, Footprint OK")
      )
      (libsource (lib "*") (part "R"))
    )
    (comp (ref "R30")
      (value "390R 1% 63mW")
      (footprint "RESC1608X40N")
      (description "Resistor, SMD")
      (fields
        (field (name "MFG") "<GENERIC>")
        (field (name "TOLERANCE") "1%")
        (field (name "FOOTPRINT CHECKED") "Assign OK, Footprint OK")
      )
      (libsource (lib "*") (part "R"))
    )
    (comp (ref "R37")
      (value "10R 1% 63mW")
      (footprint "RESC1608X40N")
      (description "Resistor, SMD")
      (fields
        (field (name "MFG") "<GENERIC>")
        (field (name "TOLERANCE") "1%")
        (field (name "FOOTPRINT CHECKED") "Assign OK, Footprint OK")
      )
      (libsource (lib "*") (part "R"))
    )
    (comp (ref "R38")
      (value "10R 1% 63mW")
      (footprint "RESC1608X40N")
      (description "Resistor, SMD")
      (fields
        (field (name "MFG") "<GENERIC>")
        (field (name "TOLERANCE") "1%")
        (field (name "FOOTPRINT CHECKED") "Assign OK, Footprint OK")
      )
      (libsource (lib "*") (part "R"))
    )
    (comp (ref "R39")
      (value "68k 1% 63mW")
      (footprint "RESC1608X40N")
      (description "Resistor, SMD")
      (fields
        (field (name "MFG") "<GENERIC>")
        (field (name "TOLERANCE") "1%")
        (field (name "FOOTPRINT CHECKED") "Assign OK, Footprint OK")
      )
      (libsource (lib "*") (part "R"))
    )
    (comp (ref "T1")
      (value "0900BL15C050")
      (footprint "BALC2012")
      (description "50:50 ohms Balun")
      (fields (field (name "MFG") "JOHANSON") (field (name "FOOTPRINT CHECKED") "Assign OK, Footprint OK"))
      (libsource (lib "sch") (part "BALUN"))
    )
    (comp (ref "TP1") (value "Test point") (footprint "TP") (libsource (lib "SensorWireless") (part "TP")))
    (comp (ref "TP2") (value "Test point") (footprint "TP") (libsource (lib "SensorWireless") (part "TP")))
    (comp (ref "TP3") (value "Test point") (footprint "TP") (libsource (lib "SensorWireless") (part "TP")))
    (comp (ref "TP4") (value "Test point") (footprint "TP") (libsource (lib "SensorWireless") (part "TP")))
    (comp (ref "TP5") (value "Test point") (footprint "TP") (libsource (lib "SensorWireless") (part "TP")))
    (comp (ref "TP6") (value "Test point") (footprint "TP") (libsource (lib "SensorWireless") (part "TP")))
    (comp (ref "TP7") (value "Test point") (footprint "TP") (libsource (lib "SensorWireless") (part "TP")))
    (comp (ref "TVS1")
      (value "PESD12VL2BT,215")
      (footprint "SOT95P230X110-3N")
      (description "TVS array")
      (fields
        (field (name "MFG") "NXP")
        (field (name "ALTIUM_VALUE") "12V")
        (field (name "FOOTPRINT CHECKED") "Assign OK, Footprint OK")
      )
      (libsource (lib "diego") (part "NUP2105L"))
    )
    (comp (ref "U1")
      (value "SE2435L-R")
      (footprint "QFN50P400X400X90-25N")
      (description "860 to 930 MHz High-Power RF Front-End Module")
      (fields (field (name "MFG") "SKYWORKS") (field (name "FOOTPRINT CHECKED") "Assign OK, Footprint OK"))
      (libsource (lib "sch") (part "SE2435L"))
    )
    (comp (ref "U2")
      (value "LD59100PUR")
      (footprint "SON65P300X300X90-9N-2")
      (description "1A ultra low-dropout regulator with reverse current protection")
      (fields (field (name "MFG") "ST") (field (name "FOOTPRINT CHECKED") "Assign OK, Footprint OK"))
      (libsource (lib "sch") (part "LD59100"))
    )
    (comp (ref "U3")
      (value "MX25R1635FM1IL0")
      (footprint "SOIC127P600X175-8N")
      (description "2.5V/3.0V 16 Mbit Serial Quad I/O (SQI) Flash Memory")
      (fields (field (name "MFG") "MACRONIX") (field (name "FOOTPRINT CHECKED") "Assign OK, Footprint OK"))
      (libsource (lib "*") (part "AT45DB321C_CNC_0"))
    )
    (comp (ref "U5")
      (value "EFR32MG13P733F512GM48-C")
      (footprint "QFN50P700X700X100-49N")
      (description "Mighty Gecko Multi-Protocol Wireless SoC Family Data Sheet")
      (fields (field (name "MFG") "SILABS") (field (name "FOOTPRINT CHECKED") "Assign OK, Footprint OK"))
      (libsource (lib "sch") (part "EFR32xG1_2.4G_SUBGHZ_QFN48"))
    )
    (comp (ref "U6")
      (value "ST3485EBDR")
      (footprint "SOIC127P600X175-8N")
      (description "Differential Bus Transceiver")
      (fields (field (name "MFG") "ST") (field (name "FOOTPRINT CHECKED") "Assign OK, Footprint OK"))
      (libsource (lib "TI Interface Line Transceiver") (part "SN75176BD"))
    )
    (comp (ref "U7")
      (value "MCP1711T-33I/OT")
      (footprint "SensorWireless:SOT95P284X122-5N")
      (description "Linear Voltage Regulator IC  1 Output  150mA SOT-25-5")
      (fields (field (name "MFG") "MICROCHIP") (field (name "FOOTPRINT CHECKED") "Assign Ok, Footprint Ok"))
      (libsource (lib "SensorWireless") (part "XC6504"))
    )
    (comp (ref "X1")
      (value "2118732-2")
      (footprint "2118732")
      (description "RF SHIELD 1.5\" X 2\" SMD")
      (fields (field (name "MFG") "TE") (field (name "FOOTPRINT CHECKED") "Assign OK, Footprint OK"))
      (libsource (lib "sch") (part "NO_PINS"))
    )
    (comp (ref "Y1")
      (value "ECS-384-10-33B-CKY")
      (footprint "XTAL3225X60N")
      (description "Crystal")
      (fields
        (field (name "MFG") "ECS")
        (field (name "ALTIUM_VALUE") "38.4MHz 10ppm CL=10pF ESR=40ohm")
        (field (name "FOOTPRINT CHECKED") "Assign OK, Footprint OK")
      )
      (libsource (lib "sch") (part "CS10-12MHz"))
    )
    (comp (ref "Y2")
      (value "CM8V-T1A-32.768kHz-12.5pF-20PPM-TA-QC")
      (footprint "XTAL2.0x1.2")
      (description "Crystal")
      (fields
        (field (name "MFG") "MICRO CRYSTAL AG")
        (field (name "ALTIUM_VALUE") "32.768kHz 12.5pF")
        (field (name "FOOTPRINT CHECKED") "Assign OK, Footprint OK")
      )
      (libsource (lib "*") (part "CS10-12MHz"))
    )
  )
  (nets
    (net (code "1") (name "+3.3V") (class "Default")
      (node (ref "C13") (pin "1") (pinfunction "1_1") (pintype "passive"))
      (node (ref "C36") (pin "1") (pinfunction "1_1") (pintype "passive"))
      (node (ref "C44") (pin "1") (pinfunction "1_1") (pintype "passive"))
      (node (ref "C45") (pin "1") (pinfunction "1_1") (pintype "passive"))
      (node (ref "C46") (pin "1") (pinfunction "1_1") (pintype "passive"))
      (node (ref "C47") (pin "1") (pinfunction "1_1") (pintype "passive"))
      (node (ref "CN3") (pin "1") (pinfunction "1_1") (pintype "passive"))
      (node (ref "CN8") (pin "10") (pinfunction "10_10") (pintype "passive"))
      (node (ref "CN9") (pin "10") (pinfunction "10_10") (pintype "passive"))
      (node (ref "R10") (pin "1") (pinfunction "1_1") (pintype "passive"))
      (node (ref "R20") (pin "1") (pinfunction "1_1") (pintype "passive"))
      (node (ref "TP6") (pin "1") (pintype "passive"))
      (node (ref "U3") (pin "3") (pinfunction "~{WP}_3") (pintype "input"))
      (node (ref "U3") (pin "8") (pinfunction "VCC_8") (pintype "power_in"))
      (node (ref "U5") (pin "34") (pinfunction "AVDD_34") (pintype "power_in"))
      (node (ref "U5") (pin "39") (pinfunction "VREGVDD_39") (pintype "power_in"))
      (node (ref "U5") (pin "42") (pinfunction "IOVDD_42") (pintype "power_in"))
      (node (ref "U6") (pin "8") (pinfunction "VCC_8") (pintype "power_in"))
      (node (ref "U7") (pin "5") (pinfunction "OUT_5") (pintype "power_in"))
    )
    (net (code "2") (name "+4.0V") (class "Default")
      (node (ref "C10") (pin "1") (pinfunction "1_1") (pintype "passive"))
      (node (ref "C14") (pin "2") (pinfunction "2_2") (pintype "passive"))
      (node (ref "C8") (pin "2") (pinfunction "2_2") (pintype "passive"))
      (node (ref "C9") (pin "2") (pinfunction "2_2") (pintype "passive"))
      (node (ref "L7") (pin "2") (pinfunction "2_2") (pintype "passive"))
      (node (ref "L8") (pin "2") (pinfunction "2_2") (pintype "passive"))
      (node (ref "L9") (pin "2") (pinfunction "2_2") (pintype "passive"))
      (node (ref "R1") (pin "2") (pinfunction "2_2") (pintype "passive"))
      (node (ref "R5") (pin "2") (pinfunction "2_2") (pintype "passive"))
      (node (ref "U2") (pin "1") (pinfunction "OUT_1") (pintype "power_in"))
    )
    (net (code "3") (name "/2G4RFIO_P") (class "Default")
      (node (ref "L14") (pin "1") (pinfunction "1_1") (pintype "passive"))
      (node (ref "U5") (pin "20") (pinfunction "PD11_20") (pintype "bidirectional"))
    )
    (net (code "4") (name "/ADC_CH1") (class "Default")
      (node (ref "C37") (pin "2") (pinfunction "2_2") (pintype "passive"))
      (node (ref "CN9") (pin "1") (pinfunction "1_1") (pintype "passive"))
      (node (ref "U5") (pin "31") (pinfunction "PB11_31") (pintype "bidirectional"))
    )
    (net (code "5") (name "/ADC_CH2") (class "Default")
      (node (ref "C38") (pin "2") (pinfunction "2_2") (pintype "passive"))
      (node (ref "CN9") (pin "3") (pinfunction "3_3") (pintype "passive"))
      (node (ref "U5") (pin "32") (pinfunction "PB12_32") (pintype "bidirectional"))
    )
    (net (code "6") (name "/ADC_CH3") (class "Default")
      (node (ref "C40") (pin "2") (pinfunction "2_2") (pintype "passive"))
      (node (ref "CN9") (pin "5") (pinfunction "5_5") (pintype "passive"))
      (node (ref "U5") (pin "33") (pinfunction "PB13_33") (pintype "bidirectional"))
    )
    (net (code "7") (name "/ADC_CH4") (class "Default")
      (node (ref "C35") (pin "2") (pinfunction "2_2") (pintype "passive"))
      (node (ref "CN9") (pin "7") (pinfunction "7_7") (pintype "passive"))
      (node (ref "R13") (pin "1") (pinfunction "1_1") (pintype "passive"))
      (node (ref "R9") (pin "2") (pinfunction "2_2") (pintype "passive"))
      (node (ref "U5") (pin "30") (pinfunction "PA5_30") (pintype "bidirectional"))
    )
    (net (code "8") (name "/ADC_CH5") (class "Default")
      (node (ref "C33") (pin "2") (pinfunction "2_2") (pintype "passive"))
      (node (ref "CN9") (pin "9") (pinfunction "9_9") (pintype "passive"))
      (node (ref "R11") (pin "1") (pinfunction "1_1") (pintype "passive"))
      (node (ref "R39") (pin "2") (pinfunction "2_2") (pintype "passive"))
      (node (ref "U5") (pin "29") (pinfunction "PA4_29") (pintype "bidirectional"))
    )
    (net (code "9") (name "/ANT") (class "Default")
      (node (ref "C1") (pin "1") (pinfunction "1_1") (pintype "passive"))
      (node (ref "CN1") (pin "5") (pinfunction "SIG_5") (pintype "passive"))
    )
    (net (code "10") (name "/ANT24") (class "Default")
      (node (ref "C28") (pin "1") (pinfunction "1_1") (pintype "passive"))
      (node (ref "CN7") (pin "1") (pinfunction "SIG_1") (pintype "passive"))
      (node (ref "L14") (pin "2") (pinfunction "2_2") (pintype "passive"))
    )
    (net (code "11") (name "/DVDD_DECOUPLE") (class "Default")
      (node (ref "C43") (pin "1") (pinfunction "1_1") (pintype "passive"))
      (node (ref "U5") (pin "41") (pinfunction "DECOUPLE_41") (pintype "power_in"))
    )
    (net (code "12") (name "/FEM_ANTSEL") (class "Default")
      (node (ref "R4") (pin "2") (pinfunction "2_2") (pintype "passive"))
      (node (ref "U5") (pin "24") (pinfunction "PD15_24") (pintype "bidirectional"))
    )
    (net (code "13") (name "/FEM_LNAEN") (class "Default")
      (node (ref "R6") (pin "2") (pinfunction "2_2") (pintype "passive"))
      (node (ref "U5") (pin "22") (pinfunction "PD13_22") (pintype "bidirectional"))
    )
    (net (code "14") (name "/FEM_PAEN") (class "Default")
      (node (ref "R7") (pin "2") (pinfunction "2_2") (pintype "passive"))
      (node (ref "U5") (pin "23") (pinfunction "PD14_23") (pintype "bidirectional"))
    )
    (net (code "15") (name "/FLASH_nCS") (class "Default")
      (node (ref "R10") (pin "2") (pinfunction "2_2") (pintype "passive"))
      (node (ref "U3") (pin "1") (pinfunction "~{CS}_1") (pintype "input"))
      (node (ref "U5") (pin "28") (pinfunction "PA3_28") (pintype "bidirectional"))
    )
    (net (code "16") (name "/FLASH_nRESET") (class "Default")
      (node (ref "R20") (pin "2") (pinfunction "2_2") (pintype "passive"))
      (node (ref "U3") (pin "7") (pinfunction "nRESET_7") (pintype "input"))
      (node (ref "U5") (pin "4") (pinfunction "PF3_4") (pintype "bidirectional"))
    )
    (net (code "17") (name "/GPIO0") (class "Default")
      (node (ref "CN8") (pin "4") (pinfunction "4_4") (pintype "passive"))
      (node (ref "U5") (pin "45") (pinfunction "PC8_45") (pintype "bidirectional"))
    )
    (net (code "18") (name "/GPIO1") (class "Default")
      (node (ref "CN8") (pin "6") (pinfunction "6_6") (pintype "passive"))
      (node (ref "U5") (pin "46") (pinfunction "PC9_46") (pintype "bidirectional"))
    )
    (net (code "19") (name "/IN0") (class "Default")
      (node (ref "CN11") (pin "1L") (pinfunction "1_1L") (pintype "passive"))
      (node (ref "R9") (pin "1") (pinfunction "1_1") (pintype "passive"))
    )
    (net (code "20") (name "/IN1") (class "Default")
      (node (ref "CN11") (pin "2L") (pinfunction "2_2L") (pintype "passive"))
      (node (ref "R39") (pin "1") (pinfunction "1_1") (pintype "passive"))
    )
    (net (code "21") (name "/LED") (class "Default")
      (node (ref "R30") (pin "1") (pinfunction "1_1") (pintype "passive"))
      (node (ref "U5") (pin "44") (pinfunction "PC7_44") (pintype "bidirectional"))
    )
    (net (code "22") (name "/LFXTAL_N") (class "Default")
      (node (ref "U5") (pin "35") (pinfunction "PB14_35") (pintype "bidirectional"))
      (node (ref "Y2") (pin "2") (pinfunction "S2_2") (pintype "passive"))
    )
    (net (code "23") (name "/LFXTAL_P") (class "Default")
      (node (ref "U5") (pin "36") (pinfunction "PB15_36") (pintype "bidirectional"))
      (node (ref "Y2") (pin "1") (pinfunction "S1_1") (pintype "passive"))
    )
    (net (code "24") (name "/MISO") (class "Default")
      (node (ref "U3") (pin "2") (pinfunction "SO_2") (pintype "tri_state"))
      (node (ref "U5") (pin "26") (pinfunction "PA1_26") (pintype "bidirectional"))
    )
    (net (code "25") (name "/MOSI") (class "Default")
      (node (ref "U3") (pin "5") (pinfunction "SI_5") (pintype "input"))
      (node (ref "U5") (pin "25") (pinfunction "PA0_25") (pintype "bidirectional"))
    )
    (net (code "26") (name "/NCP_CTS") (class "Default")
      (node (ref "CN8") (pin "3") (pinfunction "3_3") (pintype "passive"))
      (node (ref "U5") (pin "7") (pinfunction "PF6_7") (pintype "bidirectional"))
    )
    (net (code "27") (name "/NCP_PWR") (class "Default")
      (node (ref "CN9") (pin "2") (pinfunction "2_2") (pintype "passive"))
      (node (ref "R8") (pin "1") (pinfunction "1_1") (pintype "passive"))
      (node (ref "U2") (pin "5") (pinfunction "EN_5") (pintype "input"))
      (node (ref "U7") (pin "3") (pinfunction "EN_3") (pintype "input"))
    )
    (net (code "28") (name "/NCP_RTS") (class "Default")
      (node (ref "CN8") (pin "9") (pinfunction "9_9") (pintype "passive"))
      (node (ref "U5") (pin "8") (pinfunction "PF7_8") (pintype "bidirectional"))
    )
    (net (code "29") (name "/NCP_RX") (class "Default")
      (node (ref "CN8") (pin "5") (pinfunction "5_5") (pintype "passive"))
      (node (ref "U5") (pin "6") (pinfunction "PF5_6") (pintype "bidirectional"))
    )
    (net (code "30") (name "/NCP_TX") (class "Default")
      (node (ref "CN8") (pin "7") (pinfunction "7_7") (pintype "passive"))
      (node (ref "U5") (pin "5") (pinfunction "PF4_5") (pintype "bidirectional"))
    )
    (net (code "31") (name "/PAVDD") (class "Default")
      (node (ref "C24") (pin "2") (pinfunction "2_2") (pintype "passive"))
      (node (ref "C25") (pin "2") (pinfunction "2_2") (pintype "passive"))
      (node (ref "FB1") (pin "2") (pinfunction "2_2") (pintype "passive"))
      (node (ref "R12") (pin "1") (pinfunction "1_1") (pintype "passive"))
      (node (ref "T1") (pin "2") (pinfunction "2_2") (pintype "passive"))
    )
    (net (code "32") (name "/PAVDD24") (class "Default")
      (node (ref "C31") (pin "2") (pinfunction "2_2") (pintype "passive"))
      (node (ref "R12") (pin "2") (pinfunction "2_2") (pintype "passive"))
      (node (ref "U5") (pin "21") (pinfunction "PD12_21") (pintype "bidirectional"))
    )
    (net (code "33") (name "/RF1") (class "Default")
      (node (ref "C23") (pin "1") (pinfunction "1_1") (pintype "passive"))
      (node (ref "L11") (pin "1") (pinfunction "1_1") (pintype "passive"))
      (node (ref "T1") (pin "1") (pinfunction "1_1") (pintype "passive"))
    )
    (net (code "34") (name "/RF2") (class "Default")
      (node (ref "C21") (pin "1") (pinfunction "1_1") (pintype "passive"))
      (node (ref "L10") (pin "1") (pinfunction "1_1") (pintype "passive"))
      (node (ref "L11") (pin "2") (pinfunction "2_2") (pintype "passive"))
    )
    (net (code "35") (name "/RF3") (class "Default")
      (node (ref "C19") (pin "1") (pinfunction "1_1") (pintype "passive"))
      (node (ref "C20") (pin "1") (pinfunction "1_1") (pintype "passive"))
      (node (ref "L10") (pin "2") (pinfunction "2_2") (pintype "passive"))
    )
    (net (code "36") (name "/RF4") (class "Default")
      (node (ref "C17") (pin "2") (pinfunction "2_2") (pintype "passive"))
      (node (ref "C18") (pin "1") (pinfunction "1_1") (pintype "passive"))
      (node (ref "C19") (pin "2") (pinfunction "2_2") (pintype "passive"))
    )
    (net (code "37") (name "/RF5") (class "Default")
      (node (ref "C18") (pin "2") (pinfunction "2_2") (pintype "passive"))
      (node (ref "CN6") (pin "1") (pinfunction "SIG_1") (pintype "passive"))
    )
    (net (code "38") (name "/RFDIFF_N") (class "Default")
      (node (ref "C26") (pin "2") (pinfunction "2_2") (pintype "passive"))
      (node (ref "L12") (pin "2") (pinfunction "2_2") (pintype "passive"))
      (node (ref "T1") (pin "3") (pinfunction "3_3") (pintype "passive"))
    )
    (net (code "39") (name "/RFDIFF_P") (class "Default")
      (node (ref "C26") (pin "1") (pinfunction "1_1") (pintype "passive"))
      (node (ref "L13") (pin "2") (pinfunction "2_2") (pintype "passive"))
      (node (ref "T1") (pin "4") (pinfunction "4_4") (pintype "passive"))
    )
    (net (code "40") (name "/RFI_N") (class "Default")
      (node (ref "C29") (pin "2") (pinfunction "2_2") (pintype "passive"))
      (node (ref "L15") (pin "1") (pinfunction "1_1") (pintype "passive"))
      (node (ref "U5") (pin "16") (pinfunction "SUBGRFI_N_16") (pintype "input"))
    )
    (net (code "41") (name "/RFI_P") (class "Default")
      (node (ref "C30") (pin "2") (pinfunction "2_2") (pintype "passive"))
      (node (ref "L15") (pin "2") (pinfunction "2_2") (pintype "passive"))
      (node (ref "U5") (pin "15") (pinfunction "SUBGRFI_P_15") (pintype "input"))
    )
    (net (code "42") (name "/RFO_N") (class "Default")
      (node (ref "C29") (pin "1") (pinfunction "1_1") (pintype "passive"))
      (node (ref "L12") (pin "1") (pinfunction "1_1") (pintype "passive"))
      (node (ref "U5") (pin "14") (pinfunction "SUBGRFO_N_14") (pintype "output"))
    )
    (net (code "43") (name "/RFO_P") (class "Default")
      (node (ref "C30") (pin "1") (pinfunction "1_1") (pintype "passive"))
      (node (ref "L13") (pin "1") (pinfunction "1_1") (pintype "passive"))
      (node (ref "U5") (pin "13") (pinfunction "SUBGRFO_P_13") (pintype "output"))
    )
    (net (code "44") (name "/RF_ANT1") (class "Default")
      (node (ref "C1") (pin "2") (pinfunction "2_2") (pintype "passive"))
      (node (ref "C2") (pin "1") (pinfunction "1_1") (pintype "passive"))
      (node (ref "L1") (pin "2") (pinfunction "2_2") (pintype "passive"))
    )
    (net (code "45") (name "/RF_ANT1_1") (class "Default")
      (node (ref "C3") (pin "2") (pinfunction "2_2") (pintype "passive"))
      (node (ref "L1") (pin "1") (pinfunction "1_1") (pintype "passive"))
      (node (ref "L2") (pin "2") (pinfunction "2_2") (pintype "passive"))
    )
    (net (code "46") (name "/RF_ANT1_2") (class "Default")
      (node (ref "L2") (pin "1") (pinfunction "1_1") (pintype "passive"))
      (node (ref "U1") (pin "14") (pinfunction "ANT1_14") (pintype "bidirectional"))
    )
    (net (code "47") (name "/RF_ANT2") (class "Default")
      (node (ref "CN5") (pin "1") (pinfunction "SIG_1") (pintype "passive"))
      (node (ref "L6") (pin "2") (pinfunction "2_2") (pintype "passive"))
    )
    (net (code "48") (name "/RF_ANT2_1") (class "Default")
      (node (ref "C6") (pin "2") (pinfunction "2_2") (pintype "passive"))
      (node (ref "L5") (pin "2") (pinfunction "2_2") (pintype "passive"))
      (node (ref "L6") (pin "1") (pinfunction "1_1") (pintype "passive"))
    )
    (net (code "49") (name "/RF_ANT2_2") (class "Default")
      (node (ref "L5") (pin "1") (pinfunction "1_1") (pintype "passive"))
      (node (ref "U1") (pin "12") (pinfunction "ANT2_12") (pintype "bidirectional"))
    )
    (net (code "50") (name "/RF_LNA1") (class "Default")
      (node (ref "R3") (pin "1") (pinfunction "1_1") (pintype "passive"))
      (node (ref "U1") (pin "11") (pinfunction "RX_FLT_11") (pintype "output"))
    )
    (net (code "51") (name "/RF_LNA2") (class "Default")
      (node (ref "R3") (pin "2") (pinfunction "2_2") (pintype "passive"))
      (node (ref "U1") (pin "9") (pinfunction "LNA_IN_9") (pintype "input"))
    )
    (net (code "52") (name "/RF_PA1") (class "Default")
      (node (ref "C16") (pin "2") (pinfunction "2_2") (pintype "passive"))
      (node (ref "U1") (pin "5") (pinfunction "TX_FLT_5") (pintype "output"))
    )
    (net (code "53") (name "/RF_PA2") (class "Default")
      (node (ref "C16") (pin "1") (pinfunction "1_1") (pintype "passive"))
      (node (ref "U1") (pin "2") (pinfunction "PA_IN_2") (pintype "input"))
    )
    (net (code "54") (name "/RF_PA3") (class "Default")
      (node (ref "C7") (pin "1") (pinfunction "1_1") (pintype "passive"))
      (node (ref "L4") (pin "1") (pinfunction "1_1") (pintype "passive"))
      (node (ref "U1") (pin "20") (pinfunction "PA_OUT_20") (pintype "output"))
    )
    (net (code "55") (name "/RF_PA4") (class "Default")
      (node (ref "C5") (pin "1") (pinfunction "1_1") (pintype "passive"))
      (node (ref "L3") (pin "2") (pinfunction "2_2") (pintype "passive"))
      (node (ref "L4") (pin "2") (pinfunction "2_2") (pintype "passive"))
    )
    (net (code "56") (name "/RF_PA5") (class "Default")
      (node (ref "C4") (pin "1") (pinfunction "1_1") (pintype "passive"))
      (node (ref "L3") (pin "1") (pinfunction "1_1") (pintype "passive"))
      (node (ref "U1") (pin "16") (pinfunction "TX_IN_16") (pintype "input"))
    )
    (net (code "57") (name "/RS485_A") (class "Default")
      (node (ref "CN10") (pin "2L") (pinfunction "2_2L") (pintype "passive"))
      (node (ref "R38") (pin "1") (pinfunction "1_1") (pintype "passive"))
      (node (ref "TVS1") (pin "2") (pinfunction "2_2") (pintype "passive"))
    )
    (net (code "58") (name "/RS485_B") (class "Default")
      (node (ref "CN10") (pin "3L") (pinfunction "3_3L") (pintype "passive"))
      (node (ref "R37") (pin "1") (pinfunction "1_1") (pintype "passive"))
      (node (ref "TVS1") (pin "1") (pinfunction "1_1") (pintype "passive"))
    )
    (net (code "59") (name "/RS485_DE") (class "Default")
      (node (ref "R21") (pin "2") (pinfunction "2_2") (pintype "passive"))
      (node (ref "U5") (pin "3") (pinfunction "PF2_3") (pintype "bidirectional"))
      (node (ref "U6") (pin "3") (pinfunction "DE_3") (pintype "input"))
    )
    (net (code "60") (name "/RS485_N") (class "Default")
      (node (ref "R37") (pin "2") (pinfunction "2_2") (pintype "passive"))
      (node (ref "U6") (pin "7") (pinfunction "~{B}_7") (pintype "bidirectional"))
    )
    (net (code "61") (name "/RS485_P") (class "Default")
      (node (ref "R38") (pin "2") (pinfunction "2_2") (pintype "passive"))
      (node (ref "U6") (pin "6") (pinfunction "A_6") (pintype "bidirectional"))
    )
    (net (code "62") (name "/RS485_nRE") (class "Default")
      (node (ref "U5") (pin "43") (pinfunction "PC6_43") (pintype "bidirectional"))
      (node (ref "U6") (pin "2") (pinfunction "~{RE}_2") (pintype "input"))
    )
    (net (code "63") (name "/SCK") (class "Default")
      (node (ref "U3") (pin "6") (pinfunction "SCK_6") (pintype "input"))
      (node (ref "U5") (pin "27") (pinfunction "PA2_27") (pintype "bidirectional"))
    )
    (net (code "64") (name "/SWCLK") (class "Default")
      (node (ref "R16") (pin "2") (pinfunction "2_2") (pintype "passive"))
      (node (ref "U5") (pin "1") (pinfunction "PF0_1") (pintype "bidirectional"))
    )
    (net (code "65") (name "/SWDCLK_CN") (class "Default")
      (node (ref "CN3") (pin "4") (pinfunction "4_4") (pintype "passive"))
      (node (ref "R16") (pin "1") (pinfunction "1_1") (pintype "passive"))
      (node (ref "TP2") (pin "1") (pintype "passive"))
    )
    (net (code "66") (name "/SWDIO") (class "Default")
      (node (ref "R15") (pin "2") (pinfunction "2_2") (pintype "passive"))
      (node (ref "U5") (pin "2") (pinfunction "PF1_2") (pintype "bidirectional"))
    )
    (net (code "67") (name "/SWDIO_CN") (class "Default")
      (node (ref "CN3") (pin "2") (pinfunction "2_2") (pintype "passive"))
      (node (ref "R15") (pin "1") (pinfunction "1_1") (pintype "passive"))
      (node (ref "TP1") (pin "1") (pintype "passive"))
    )
    (net (code "68") (name "/UART_RX") (class "Default")
      (node (ref "CN9") (pin "4") (pinfunction "4_4") (pintype "passive"))
      (node (ref "R18") (pin "2") (pinfunction "2_2") (pintype "passive"))
      (node (ref "U5") (pin "47") (pinfunction "PC10_47") (pintype "bidirectional"))
      (node (ref "U6") (pin "1") (pinfunction "R_1") (pintype "tri_state"))
    )
    (net (code "69") (name "/UART_RX_CN") (class "Default")
      (node (ref "CN3") (pin "9") (pinfunction "9_9") (pintype "passive"))
      (node (ref "R18") (pin "1") (pinfunction "1_1") (pintype "passive"))
      (node (ref "TP4") (pin "1") (pintype "passive"))
    )
    (net (code "70") (name "/UART_TX") (class "Default")
      (node (ref "CN9") (pin "6") (pinfunction "6_6") (pintype "passive"))
      (node (ref "R19") (pin "2") (pinfunction "2_2") (pintype "passive"))
      (node (ref "U5") (pin "48") (pinfunction "PC11_48") (pintype "bidirectional"))
      (node (ref "U6") (pin "4") (pinfunction "D_4") (pintype "input"))
    )
    (net (code "71") (name "/UART_TX_CN") (class "Default")
      (node (ref "CN3") (pin "7") (pinfunction "7_7") (pintype "passive"))
      (node (ref "R19") (pin "1") (pinfunction "1_1") (pintype "passive"))
      (node (ref "TP5") (pin "1") (pintype "passive"))
    )
    (net (code "72") (name "/VDCDC") (class "Default")
      (node (ref "C39") (pin "1") (pinfunction "1_1") (pintype "passive"))
      (node (ref "C42") (pin "2") (pinfunction "2_2") (pintype "passive"))
      (node (ref "FB1") (pin "1") (pinfunction "1_1") (pintype "passive"))
      (node (ref "FB2") (pin "2") (pinfunction "2_2") (pintype "passive"))
      (node (ref "L16") (pin "2") (pinfunction "2_2") (pintype "passive"))
      (node (ref "U5") (pin "40") (pinfunction "DVDD_40") (pintype "power_in"))
    )
    (net (code "73") (name "/VDDRF") (class "Default")
      (node (ref "C34") (pin "2") (pinfunction "2_2") (pintype "passive"))
      (node (ref "FB2") (pin "1") (pinfunction "1_1") (pintype "passive"))
      (node (ref "U5") (pin "9") (pinfunction "RFVDD_9") (pintype "power_in"))
    )
    (net (code "74") (name "/VREGSW") (class "Default")
      (node (ref "L16") (pin "1") (pinfunction "1_1") (pintype "passive"))
      (node (ref "U5") (pin "38") (pinfunction "VREGSW_38") (pintype "power_in"))
    )
    (net (code "75") (name "/XIN") (class "Default")
      (node (ref "U5") (pin "10") (pinfunction "HFXTAL_N_10") (pintype "input"))
      (node (ref "Y1") (pin "1") (pinfunction "S1_1") (pintype "passive"))
    )
    (net (code "76") (name "/XOUT") (class "Default")
      (node (ref "U5") (pin "11") (pinfunction "HFXTAL_P_11") (pintype "output"))
      (node (ref "Y1") (pin "3") (pinfunction "S2_3") (pintype "passive"))
    )
    (net (code "77") (name "/nRESET") (class "Default")
      (node (ref "C27") (pin "2") (pinfunction "2_2") (pintype "passive"))
      (node (ref "CN8") (pin "8") (pinfunction "8_8") (pintype "passive"))
      (node (ref "R17") (pin "2") (pinfunction "2_2") (pintype "passive"))
      (node (ref "U5") (pin "12") (pinfunction "nRESET_12") (pintype "input"))
    )
    (net (code "78") (name "/nRESET_CN") (class "Default")
      (node (ref "CN3") (pin "10") (pinfunction "10_10") (pintype "passive"))
      (node (ref "R17") (pin "1") (pinfunction "1_1") (pintype "passive"))
      (node (ref "TP3") (pin "1") (pintype "passive"))
    )
    (net (code "79") (name "GND") (class "Default")
      (node (ref "C10") (pin "2") (pinfunction "2_2") (pintype "passive"))
      (node (ref "C11") (pin "1") (pinfunction "1_1") (pintype "passive"))
      (node (ref "C12") (pin "1") (pinfunction "1_1") (pintype "passive"))
      (node (ref "C13") (pin "2") (pinfunction "2_2") (pintype "passive"))
      (node (ref "C14") (pin "1") (pinfunction "1_1") (pintype "passive"))
      (node (ref "C15") (pin "2") (pinfunction "2_2") (pintype "passive"))
      (node (ref "C20") (pin "2") (pinfunction "2_2") (pintype "passive"))
      (node (ref "C21") (pin "2") (pinfunction "2_2") (pintype "passive"))
      (node (ref "C23") (pin "2") (pinfunction "2_2") (pintype "passive"))
      (node (ref "C24") (pin "1") (pinfunction "1_1") (pintype "passive"))
      (node (ref "C25") (pin "1") (pinfunction "1_1") (pintype "passive"))
      (node (ref "C27") (pin "1") (pinfunction "1_1") (pintype "passive"))
      (node (ref "C28") (pin "2") (pinfunction "2_2") (pintype "passive"))
      (node (ref "C3") (pin "1") (pinfunction "1_1") (pintype "passive"))
      (node (ref "C31") (pin "1") (pinfunction "1_1") (pintype "passive"))
      (node (ref "C33") (pin "1") (pinfunction "1_1") (pintype "passive"))
      (node (ref "C34") (pin "1") (pinfunction "1_1") (pintype "passive"))
      (node (ref "C35") (pin "1") (pinfunction "1_1") (pintype "passive"))
      (node (ref "C36") (pin "2") (pinfunction "2_2") (pintype "passive"))
      (node (ref "C37") (pin "1") (pinfunction "1_1") (pintype "passive"))
      (node (ref "C38") (pin "1") (pinfunction "1_1") (pintype "passive"))
      (node (ref "C39") (pin "2") (pinfunction "2_2") (pintype "passive"))
      (node (ref "C4") (pin "2") (pinfunction "2_2") (pintype "passive"))
      (node (ref "C40") (pin "1") (pinfunction "1_1") (pintype "passive"))
      (node (ref "C42") (pin "1") (pinfunction "1_1") (pintype "passive"))
      (node (ref "C43") (pin "2") (pinfunction "2_2") (pintype "passive"))
      (node (ref "C44") (pin "2") (pinfunction "2_2") (pintype "passive"))
      (node (ref "C45") (pin "2") (pinfunction "2_2") (pintype "passive"))
      (node (ref "C46") (pin "2") (pinfunction "2_2") (pintype "passive"))
      (node (ref "C47") (pin "2") (pinfunction "2_2") (pintype "passive"))
      (node (ref "C5") (pin "2") (pinfunction "2_2") (pintype "passive"))
      (node (ref "C6") (pin "1") (pinfunction "1_1") (pintype "passive"))
      (node (ref "C7") (pin "2") (pinfunction "2_2") (pintype "passive"))
      (node (ref "C8") (pin "1") (pinfunction "1_1") (pintype "passive"))
      (node (ref "C9") (pin "1") (pinfunction "1_1") (pintype "passive"))
      (node (ref "CN1") (pin "1") (pinfunction "GND_1") (pintype "passive"))
      (node (ref "CN1") (pin "2") (pinfunction "GND_2") (pintype "passive"))
      (node (ref "CN1") (pin "3") (pinfunction "GND_3") (pintype "passive"))
      (node (ref "CN1") (pin "4") (pinfunction "GND_4") (pintype "passive"))
      (node (ref "CN10") (pin "1L") (pinfunction "1_1L") (pintype "passive"))
      (node (ref "CN2") (pin "2L") (pinfunction "2_2L") (pintype "passive"))
      (node (ref "CN3") (pin "3") (pinfunction "3_3") (pintype "passive"))
      (node (ref "CN3") (pin "5") (pinfunction "5_5") (pintype "passive"))
      (node (ref "CN4") (pin "2") (pinfunction "GND_2") (pintype "passive"))
      (node (ref "CN4") (pin "3") (pinfunction "GND_3") (pintype "passive"))
      (node (ref "CN5") (pin "2") (pinfunction "GND_2") (pintype "passive"))
      (node (ref "CN5") (pin "3") (pinfunction "GND_3") (pintype "passive"))
      (node (ref "CN6") (pin "2") (pinfunction "GND_2") (pintype "passive"))
      (node (ref "CN6") (pin "3") (pinfunction "GND_3") (pintype "passive"))
      (node (ref "CN7") (pin "2") (pinfunction "GND_2") (pintype "passive"))
      (node (ref "CN7") (pin "3") (pinfunction "GND_3") (pintype "passive"))
      (node (ref "CN8") (pin "1") (pinfunction "1_1") (pintype "passive"))
      (node (ref "CN9") (pin "8") (pinfunction "8_8") (pintype "passive"))
      (node (ref "LED1") (pin "2") (pinfunction "ANODE_2") (pintype "passive"))
      (node (ref "R11") (pin "2") (pinfunction "2_2") (pintype "passive"))
      (node (ref "R13") (pin "2") (pinfunction "2_2") (pintype "passive"))
      (node (ref "R14") (pin "1") (pinfunction "1_1") (pintype "passive"))
      (node (ref "R2") (pin "1") (pinfunction "1_1") (pintype "passive"))
      (node (ref "R21") (pin "1") (pinfunction "1_1") (pintype "passive"))
      (node (ref "T1") (pin "5") (pinfunction "5_5") (pintype "passive"))
      (node (ref "TP7") (pin "1") (pintype "passive"))
      (node (ref "TVS1") (pin "3") (pinfunction "3_3") (pintype "passive"))
      (node (ref "U1") (pin "0") (pinfunction "EP_0") (pintype "power_in"))
      (node (ref "U1") (pin "10") (pinfunction "NC_10") (pintype "passive"))
      (node (ref "U1") (pin "13") (pinfunction "NC_13") (pintype "passive"))
      (node (ref "U1") (pin "15") (pinfunction "NC_15") (pintype "passive"))
      (node (ref "U1") (pin "17") (pinfunction "NC_17") (pintype "passive"))
      (node (ref "U1") (pin "18") (pinfunction "NC_18") (pintype "passive"))
      (node (ref "U1") (pin "19") (pinfunction "NC_19") (pintype "passive"))
      (node (ref "U1") (pin "22") (pinfunction "NC_22") (pintype "passive"))
      (node (ref "U1") (pin "8") (pinfunction "GND_8") (pintype "power_in"))
      (node (ref "U2") (pin "0") (pinfunction "EP_0") (pintype "power_in"))
      (node (ref "U2") (pin "4") (pinfunction "GND_4") (pintype "power_in"))
      (node (ref "U3") (pin "4") (pinfunction "GND_4") (pintype "power_in"))
      (node (ref "U5") (pin "0") (pinfunction "GND_0") (pintype "power_in"))
      (node (ref "U5") (pin "17") (pinfunction "RFVSS_17") (pintype "power_in"))
      (node (ref "U5") (pin "18") (pinfunction "PD9_18") (pintype "bidirectional"))
      (node (ref "U5") (pin "19") (pinfunction "PD10_19") (pintype "bidirectional"))
      (node (ref "U5") (pin "37") (pinfunction "VREGVSS_37") (pintype "power_in"))
      (node (ref "U6") (pin "5") (pinfunction "GND_5") (pintype "power_in"))
      (node (ref "U7") (pin "2") (pinfunction "GND_2") (pintype "power_in"))
      (node (ref "X1") (pin "1") (pinfunction "PIN_1") (pintype "passive"))
      (node (ref "Y1") (pin "2") (pinfunction "GND_2") (pintype "passive"))
      (node (ref "Y1") (pin "4") (pinfunction "GND_4") (pintype "passive"))
    )
    (net (code "80") (name "Net-(CN4-SIG)") (class "Default")
      (node (ref "C2") (pin "2") (pinfunction "2_2") (pintype "passive"))
      (node (ref "CN4") (pin "1") (pinfunction "SIG_1") (pintype "passive"))
    )
    (net (code "81") (name "Net-(LED1-CATHODE)") (class "Default")
      (node (ref "LED1") (pin "1") (pinfunction "CATHODE_1") (pintype "passive"))
      (node (ref "R30") (pin "2") (pinfunction "2_2") (pintype "passive"))
    )
    (net (code "82") (name "Net-(U1-ANT_SEL)") (class "Default")
      (node (ref "R4") (pin "1") (pinfunction "1_1") (pintype "passive"))
      (node (ref "U1") (pin "7") (pinfunction "ANT_SEL_7") (pintype "input"))
    )
    (net (code "83") (name "Net-(U1-CPS)") (class "Default")
      (node (ref "R6") (pin "1") (pinfunction "1_1") (pintype "passive"))
      (node (ref "U1") (pin "3") (pinfunction "CPS_3") (pintype "input"))
    )
    (net (code "84") (name "Net-(U1-CSD)") (class "Default")
      (node (ref "R5") (pin "1") (pinfunction "1_1") (pintype "passive"))
      (node (ref "U1") (pin "1") (pinfunction "CSD_1") (pintype "input"))
    )
    (net (code "85") (name "Net-(U1-CTX)") (class "Default")
      (node (ref "R7") (pin "1") (pinfunction "1_1") (pintype "passive"))
      (node (ref "U1") (pin "4") (pinfunction "CTX_4") (pintype "input"))
    )
    (net (code "86") (name "Net-(U1-TR)") (class "Default")
      (node (ref "C17") (pin "1") (pinfunction "1_1") (pintype "passive"))
      (node (ref "U1") (pin "6") (pinfunction "TR_6") (pintype "bidirectional"))
    )
    (net (code "87") (name "Net-(U1-VCC0)") (class "Default")
      (node (ref "C11") (pin "2") (pinfunction "2_2") (pintype "passive"))
      (node (ref "L8") (pin "1") (pinfunction "1_1") (pintype "passive"))
      (node (ref "U1") (pin "23") (pinfunction "VCC0_23") (pintype "power_in"))
    )
    (net (code "88") (name "Net-(U1-VCC1)") (class "Default")
      (node (ref "C12") (pin "2") (pinfunction "2_2") (pintype "passive"))
      (node (ref "L9") (pin "1") (pinfunction "1_1") (pintype "passive"))
      (node (ref "U1") (pin "24") (pinfunction "VCC1_24") (pintype "power_in"))
    )
    (net (code "89") (name "Net-(U1-VCC2)") (class "Default")
      (node (ref "L7") (pin "1") (pinfunction "1_1") (pintype "passive"))
      (node (ref "U1") (pin "21") (pinfunction "VCC2_21") (pintype "power_in"))
    )
    (net (code "90") (name "Net-(U2-FB)") (class "Default")
      (node (ref "R1") (pin "1") (pinfunction "1_1") (pintype "passive"))
      (node (ref "R14") (pin "2") (pinfunction "2_2") (pintype "passive"))
      (node (ref "R2") (pin "2") (pinfunction "2_2") (pintype "passive"))
      (node (ref "U2") (pin "3") (pinfunction "FB_3") (pintype "input"))
    )
    (net (code "91") (name "VIN") (class "Default")
      (node (ref "C15") (pin "1") (pinfunction "1_1") (pintype "passive"))
      (node (ref "CN2") (pin "1L") (pinfunction "1_1L") (pintype "passive"))
      (node (ref "CN8") (pin "2") (pinfunction "2_2") (pintype "passive"))
      (node (ref "R8") (pin "2") (pinfunction "2_2") (pintype "passive"))
      (node (ref "U2") (pin "8") (pinfunction "IN_8") (pintype "passive"))
      (node (ref "U7") (pin "1") (pinfunction "IN_1") (pintype "power_in"))
    )
    (net (code "92") (name "unconnected-(CN3-Pad6)") (class "Default")
      (node (ref "CN3") (pin "6") (pinfunction "6_6") (pintype "passive+no_connect"))
    )
    (net (code "93") (name "unconnected-(CN3-Pad8)") (class "Default")
      (node (ref "CN3") (pin "8") (pinfunction "8_8") (pintype "passive+no_connect"))
    )
    (net (code "94") (name "unconnected-(U2-NC-Pad2)") (class "Default")
      (node (ref "U2") (pin "2") (pinfunction "NC_2") (pintype "passive+no_connect"))
    )
    (net (code "95") (name "unconnected-(U2-NC-Pad6)") (class "Default")
      (node (ref "U2") (pin "6") (pinfunction "NC_6") (pintype "passive+no_connect"))
    )
    (net (code "96") (name "unconnected-(U2-NC-Pad7)") (class "Default")
      (node (ref "U2") (pin "7") (pinfunction "NC_7") (pintype "passive+no_connect"))
    )
    (net (code "97") (name "unconnected-(U7-NC-Pad4)") (class "Default")
      (node (ref "U7") (pin "4") (pinfunction "NC_4") (pintype "tri_state+no_connect"))
    )
  )
)
